# aKaReZa75_eBoard_STM32F103C8__STM32F103C.net
KiCad netlist of a schematic drawn in Altium Designer
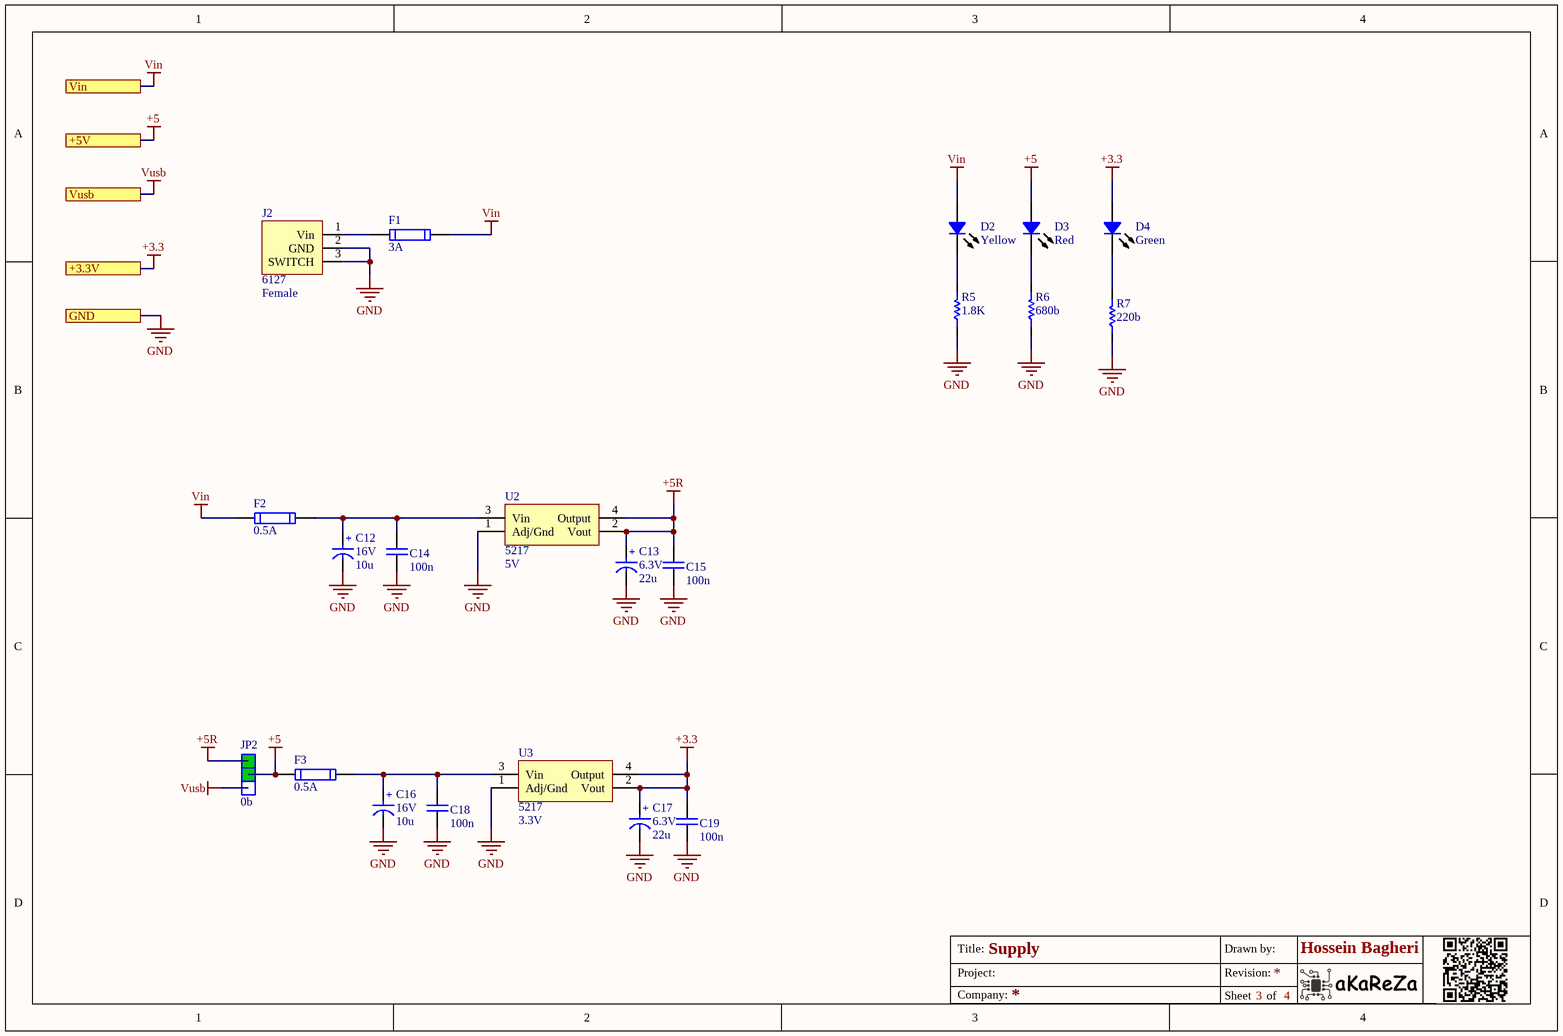
[diagram p0: aKaReZa75_eBoard_STM32F103C8__STM32F103C8__Supply.SchDoc]

(export (version "E")
  (design (tool "Eeschema 10.0.6"))
  (components
    (comp (ref "C12")
      (value "10u")
      (footprint "SMT_C_Tantalum_A")
      (description "Tantalum Capacitor,TAJ Series-SMD")
      (fields (field (name "RATING") "16V") (field (name "VALIDATION") "Valid"))
      (libsource (lib "aKaReZa") (part "Cap_Tantalum"))
    )
    (comp (ref "C13")
      (value "22u")
      (footprint "SMT_C_Tantalum_A")
      (description "Tantalum Capacitor,TAJ Series-SMD")
      (fields (field (name "RATING") "6.3V") (field (name "VALIDATION") "Valid"))
      (libsource (lib "aKaReZa") (part "Cap_Tantalum"))
    )
    (comp (ref "C14")
      (value "100n")
      (footprint "CAP 1206/3216")
      (description "Bipolar ceramic capacitor SMD")
      (fields (field (name "VALIDATION") "Valid"))
      (libsource (lib "aKaReZa") (part "Cap_Multi_SMD_100nF_1206"))
    )
    (comp (ref "C15")
      (value "100n")
      (footprint "CAP 1206/3216")
      (description "Bipolar ceramic capacitor SMD")
      (fields (field (name "VALIDATION") "Valid"))
      (libsource (lib "aKaReZa") (part "Cap_Multi_SMD_100nF_1206"))
    )
    (comp (ref "C16")
      (value "10u")
      (footprint "SMT_C_Tantalum_A")
      (description "Tantalum Capacitor,TAJ Series-SMD")
      (fields (field (name "RATING") "16V") (field (name "VALIDATION") "Valid"))
      (libsource (lib "aKaReZa") (part "Cap_Tantalum"))
    )
    (comp (ref "C17")
      (value "22u")
      (footprint "SMT_C_Tantalum_A")
      (description "Tantalum Capacitor,TAJ Series-SMD")
      (fields (field (name "RATING") "6.3V") (field (name "VALIDATION") "Valid"))
      (libsource (lib "aKaReZa") (part "Cap_Tantalum"))
    )
    (comp (ref "C18")
      (value "100n")
      (footprint "CAP 1206/3216")
      (description "Bipolar ceramic capacitor SMD")
      (fields (field (name "VALIDATION") "Valid"))
      (libsource (lib "aKaReZa") (part "Cap_Multi_SMD_100nF_1206"))
    )
    (comp (ref "C19")
      (value "100n")
      (footprint "CAP 1206/3216")
      (description "Bipolar ceramic capacitor SMD")
      (fields (field (name "VALIDATION") "Valid"))
      (libsource (lib "aKaReZa") (part "Cap_Multi_SMD_100nF_1206"))
    )
    (comp (ref "D2")
      (value "Yellow")
      (footprint "LED 0805/2012 YELLOW")
      (description "LED")
      (fields (field (name "VALIDATION") "Valid"))
      (libsource (lib "aKaReZa") (part "Semi_LED_SMD"))
    )
    (comp (ref "D3")
      (value "Red")
      (footprint "LED 0805/2012 RED")
      (description "LED")
      (fields (field (name "VALIDATION") "Valid"))
      (libsource (lib "aKaReZa") (part "Semi_LED_SMD"))
    )
    (comp (ref "D4")
      (value "Green")
      (footprint "LED 0805/2012 GREEN")
      (description "LED")
      (fields (field (name "VALIDATION") "Valid"))
      (libsource (lib "aKaReZa") (part "Semi_LED_SMD"))
    )
    (comp (ref "F1")
      (value "3A")
      (footprint "1206_F")
      (description "Short circiut  protection")
      (fields (field (name "VALIDATION") "Valid"))
      (libsource (lib "aKaReZa") (part "Other_Elec_Fuse_SMD"))
    )
    (comp (ref "F2")
      (value "0.5A")
      (footprint "1206_F")
      (description "Short circiut  protection")
      (fields (field (name "VALIDATION") "Valid"))
      (libsource (lib "aKaReZa") (part "Other_Elec_Fuse_SMD"))
    )
    (comp (ref "F3")
      (value "0.5A")
      (footprint "1206_F")
      (description "Short circiut  protection")
      (fields (field (name "VALIDATION") "Valid"))
      (libsource (lib "aKaReZa") (part "Other_Elec_Fuse_SMD"))
    )
    (comp (ref "J2")
      (value "Female")
      (footprint "Power Jack BIG")
      (description "Power Jack")
      (fields (field (name "INFLOW") "6127") (field (name "VALIDATION") "Valid"))
      (libsource (lib "aKaReZa") (part "Con_Power_Jack"))
    )
    (comp (ref "JP2")
      (value "0b")
      (footprint "jumper selector")
      (description "Jumper Selector")
      (fields (field (name "VALIDATION") "NT"))
      (libsource (lib "aKaReZa") (part "SW_Other_JSelector_Dip"))
    )
    (comp (ref "R5")
      (value "1.8K")
      (footprint "RES 0805 (2012X06L)")
      (description "Resistor")
      (fields (field (name "VALIDATION") "Valid"))
      (libsource (lib "aKaReZa") (part "Res_SMD_0805"))
    )
    (comp (ref "R6")
      (value "680b")
      (footprint "RES 0805 (2012X06L)")
      (description "Resistor")
      (fields (field (name "VALIDATION") "Valid"))
      (libsource (lib "aKaReZa") (part "Res_SMD_0805"))
    )
    (comp (ref "R7")
      (value "220b")
      (footprint "RES 0805 (2012X06L)")
      (description "Resistor")
      (fields (field (name "VALIDATION") "Valid"))
      (libsource (lib "aKaReZa") (part "Res_SMD_0805"))
    )
    (comp (ref "U2")
      (value "5V")
      (footprint "SOT223_M")
      (description "1'A Positive voltage regulator")
      (fields (field (name "INFLOW") "5217") (field (name "VALIDATION") "Valid"))
      (libsource (lib "aKaReZa") (part "IC_Reg_AMS1117_3.3"))
    )
    (comp (ref "U3")
      (value "3.3V")
      (footprint "SOT223_M")
      (description "1'A Positive voltage regulator")
      (fields (field (name "INFLOW") "5217") (field (name "VALIDATION") "Valid"))
      (libsource (lib "aKaReZa") (part "IC_Reg_AMS1117_3.3"))
    )
  )
  (nets
    (net (code "1") (name "+3.3") (class "Default")
      (node (ref "C17") (pin "1") (pinfunction "+_1") (pintype "passive"))
      (node (ref "C19") (pin "1") (pinfunction "1_1") (pintype "passive"))
      (node (ref "D4") (pin "1") (pinfunction "1_1") (pintype "passive"))
      (node (ref "U3") (pin "2") (pinfunction "Vout_2") (pintype "passive"))
      (node (ref "U3") (pin "4") (pinfunction "Output_4") (pintype "passive"))
    )
    (net (code "2") (name "+5") (class "Default")
      (node (ref "D3") (pin "1") (pinfunction "1_1") (pintype "passive"))
      (node (ref "F3") (pin "1") (pinfunction "1_1") (pintype "passive"))
      (node (ref "JP2") (pin "2") (pinfunction "2_2") (pintype "passive"))
    )
    (net (code "3") (name "+5R") (class "Default")
      (node (ref "C13") (pin "1") (pinfunction "+_1") (pintype "passive"))
      (node (ref "C15") (pin "1") (pinfunction "1_1") (pintype "passive"))
      (node (ref "JP2") (pin "1") (pinfunction "1_1") (pintype "passive"))
      (node (ref "U2") (pin "2") (pinfunction "Vout_2") (pintype "passive"))
      (node (ref "U2") (pin "4") (pinfunction "Output_4") (pintype "passive"))
    )
    (net (code "4") (name "GND") (class "Default")
      (node (ref "C12") (pin "2") (pinfunction "-_2") (pintype "passive"))
      (node (ref "C13") (pin "2") (pinfunction "-_2") (pintype "passive"))
      (node (ref "C14") (pin "2") (pinfunction "2_2") (pintype "passive"))
      (node (ref "C15") (pin "2") (pinfunction "2_2") (pintype "passive"))
      (node (ref "C16") (pin "2") (pinfunction "-_2") (pintype "passive"))
      (node (ref "C17") (pin "2") (pinfunction "-_2") (pintype "passive"))
      (node (ref "C18") (pin "2") (pinfunction "2_2") (pintype "passive"))
      (node (ref "C19") (pin "2") (pinfunction "2_2") (pintype "passive"))
      (node (ref "J2") (pin "2") (pinfunction "GND_2") (pintype "passive"))
      (node (ref "J2") (pin "3") (pinfunction "SWITCH_3") (pintype "passive"))
      (node (ref "R5") (pin "1") (pinfunction "1_1") (pintype "passive"))
      (node (ref "R6") (pin "1") (pinfunction "1_1") (pintype "passive"))
      (node (ref "R7") (pin "1") (pinfunction "1_1") (pintype "passive"))
      (node (ref "U2") (pin "1") (pinfunction "Adj/Gnd_1") (pintype "passive"))
      (node (ref "U3") (pin "1") (pinfunction "Adj/Gnd_1") (pintype "passive"))
    )
    (net (code "5") (name "Net-(C12-+)") (class "Default")
      (node (ref "C12") (pin "1") (pinfunction "+_1") (pintype "passive"))
      (node (ref "C14") (pin "1") (pinfunction "1_1") (pintype "passive"))
      (node (ref "F2") (pin "2") (pinfunction "2_2") (pintype "passive"))
      (node (ref "U2") (pin "3") (pinfunction "Vin_3") (pintype "passive"))
    )
    (net (code "6") (name "Net-(C16-+)") (class "Default")
      (node (ref "C16") (pin "1") (pinfunction "+_1") (pintype "passive"))
      (node (ref "C18") (pin "1") (pinfunction "1_1") (pintype "passive"))
      (node (ref "F3") (pin "2") (pinfunction "2_2") (pintype "passive"))
      (node (ref "U3") (pin "3") (pinfunction "Vin_3") (pintype "passive"))
    )
    (net (code "7") (name "Net-(D2-Pad2)") (class "Default")
      (node (ref "D2") (pin "2") (pinfunction "2_2") (pintype "passive"))
      (node (ref "R5") (pin "2") (pinfunction "2_2") (pintype "passive"))
    )
    (net (code "8") (name "Net-(D3-Pad2)") (class "Default")
      (node (ref "D3") (pin "2") (pinfunction "2_2") (pintype "passive"))
      (node (ref "R6") (pin "2") (pinfunction "2_2") (pintype "passive"))
    )
    (net (code "9") (name "Net-(D4-Pad2)") (class "Default")
      (node (ref "D4") (pin "2") (pinfunction "2_2") (pintype "passive"))
      (node (ref "R7") (pin "2") (pinfunction "2_2") (pintype "passive"))
    )
    (net (code "10") (name "Net-(J2-Vin)") (class "Default")
      (node (ref "F1") (pin "1") (pinfunction "1_1") (pintype "passive"))
      (node (ref "J2") (pin "1") (pinfunction "Vin_1") (pintype "passive"))
    )
    (net (code "11") (name "Vin") (class "Default")
      (node (ref "D2") (pin "1") (pinfunction "1_1") (pintype "passive"))
      (node (ref "F1") (pin "2") (pinfunction "2_2") (pintype "passive"))
      (node (ref "F2") (pin "1") (pinfunction "1_1") (pintype "passive"))
    )
    (net (code "12") (name "Vusb") (class "Default")
      (node (ref "JP2") (pin "3") (pinfunction "3_3") (pintype "passive"))
    )
  )
)
